# LED_Sectional.net
KiCad netlist of a schematic drawn in EAGLE
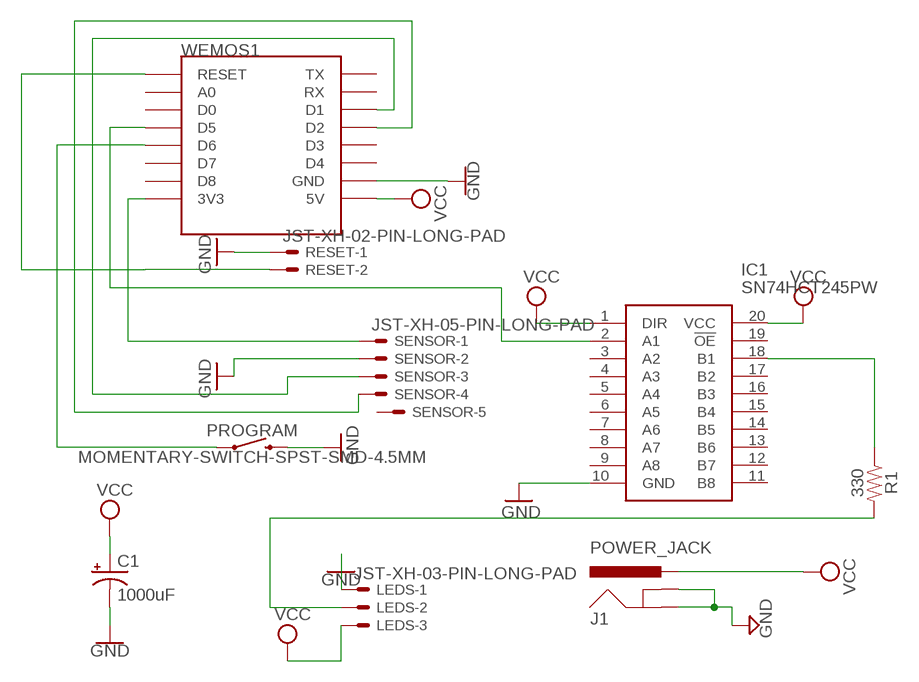
[diagram p0: schematic, sheet 1]

(export (version "E")
  (design (tool "Eeschema 10.0.6"))
  (components
    (comp (ref "C1")
      (value "1000uF")
      (footprint "eagle-import:CT7343")
      (libsource (lib "eagle-import") (part "CPOL-USCT7343"))
    )
    (comp (ref "IC1")
      (value "SN74HCT245PW")
      (footprint "eagle-import:SOP65P640X120-20N")
      (fields
        (field (name "MOUSER_PART_NUMBER") "595-SN74HCT245PW")
        (field (name "RS_PART_NUMBER") "6632287")
      )
      (libsource (lib "eagle-import") (part "SN74HCT245PW"))
    )
    (comp (ref "J1")
      (value "POWER_JACK")
      (footprint "eagle-import:POWER_JACK_PTH")
      (libsource (lib "eagle-import") (part "POWER_JACK"))
    )
    (comp (ref "LEDS")
      (value "JST-XH-03-PIN-LONG-PAD")
      (footprint "eagle-import:JST-XH-03-PACKAGE-LONG-PAD")
      (libsource (lib "eagle-import") (part "JST-XH-03-PIN-LONG-PAD"))
    )
    (comp (ref "PROGRAM")
      (value "MOMENTARY-SWITCH-SPST-SMD-4.5MM")
      (footprint "eagle-import:TACTILE_SWITCH_SMD_4.5MM")
      (libsource (lib "eagle-import") (part "MOMENTARY-SWITCH-SPST-SMD-4.5MM"))
    )
    (comp (ref "R1")
      (value "330")
      (footprint "eagle-import:0603")
      (libsource (lib "eagle-import") (part "330OHM-0603-1/10W-1%"))
    )
    (comp (ref "RESET")
      (value "JST-XH-02-PIN-LONG-PAD")
      (footprint "eagle-import:JST-XH-02-PACKAGE-LONG-PAD")
      (libsource (lib "eagle-import") (part "JST-XH-02-PIN-LONG-PAD"))
    )
    (comp (ref "SENSOR")
      (value "JST-XH-05-PIN-LONG-PAD")
      (footprint "eagle-import:JST-XH-05-PACKAGE-LONG-PAD")
      (libsource (lib "eagle-import") (part "JST-XH-05-PIN-LONG-PAD"))
    )
    (comp (ref "WEMOS1")
      (value "WEMOS-D1-MINI")
      (footprint "eagle-import:WEMOS-D1-MINI")
      (libsource (lib "eagle-import") (part "WEMOS-D1-MINI"))
    )
  )
  (nets
    (net (code "1") (name "GND") (class "Default")
      (node (ref "C1") (pin "-") (pinfunction "-_-") (pintype "passive"))
      (node (ref "IC1") (pin "10") (pinfunction "GND_10") (pintype "bidirectional"))
      (node (ref "J1") (pin "GND") (pinfunction "GND_GND") (pintype "bidirectional"))
      (node (ref "J1") (pin "GNDBREAK") (pinfunction "GNDBREAK_GNDBREAK") (pintype "bidirectional"))
      (node (ref "LEDS") (pin "1") (pinfunction "S_1") (pintype "passive"))
      (node (ref "PROGRAM") (pin "1") (pinfunction "2_1") (pintype "passive"))
      (node (ref "PROGRAM") (pin "4") (pinfunction "2_4") (pintype "passive"))
      (node (ref "RESET") (pin "1") (pinfunction "S_1") (pintype "passive"))
      (node (ref "SENSOR") (pin "2") (pinfunction "S_2") (pintype "passive"))
      (node (ref "WEMOS1") (pin "GND") (pinfunction "GND_GND") (pintype "bidirectional"))
    )
    (net (code "2") (name "Net-(IC1-A1)") (class "Default")
      (node (ref "IC1") (pin "2") (pinfunction "A1_2") (pintype "bidirectional"))
      (node (ref "WEMOS1") (pin "D5") (pinfunction "D5_D5") (pintype "bidirectional"))
    )
    (net (code "3") (name "Net-(IC1-B1)") (class "Default")
      (node (ref "IC1") (pin "18") (pinfunction "B1_18") (pintype "bidirectional"))
      (node (ref "R1") (pin "1") (pinfunction "1_1") (pintype "passive"))
    )
    (net (code "4") (name "Net-(LEDSB-S)") (class "Default")
      (node (ref "LEDS") (pin "2") (pinfunction "S_2") (pintype "passive"))
      (node (ref "R1") (pin "2") (pinfunction "2_2") (pintype "passive"))
    )
    (net (code "5") (name "Net-(PROGRAM-1-Pad2)") (class "Default")
      (node (ref "PROGRAM") (pin "2") (pinfunction "1_2") (pintype "passive"))
      (node (ref "PROGRAM") (pin "3") (pinfunction "1_3") (pintype "passive"))
      (node (ref "WEMOS1") (pin "D6") (pinfunction "D6_D6") (pintype "bidirectional"))
    )
    (net (code "6") (name "Net-(RESETB-S)") (class "Default")
      (node (ref "RESET") (pin "2") (pinfunction "S_2") (pintype "passive"))
      (node (ref "WEMOS1") (pin "RESET") (pinfunction "RESET_RESET") (pintype "bidirectional"))
    )
    (net (code "7") (name "Net-(SENSORA-S)") (class "Default")
      (node (ref "SENSOR") (pin "1") (pinfunction "S_1") (pintype "passive"))
      (node (ref "WEMOS1") (pin "3V3") (pinfunction "3V3_3V3") (pintype "bidirectional"))
    )
    (net (code "8") (name "Net-(SENSORC-S)") (class "Default")
      (node (ref "SENSOR") (pin "3") (pinfunction "S_3") (pintype "passive"))
      (node (ref "WEMOS1") (pin "D1") (pinfunction "D1_D1") (pintype "bidirectional"))
    )
    (net (code "9") (name "Net-(SENSORD-S)") (class "Default")
      (node (ref "SENSOR") (pin "4") (pinfunction "S_4") (pintype "passive"))
      (node (ref "WEMOS1") (pin "D2") (pinfunction "D2_D2") (pintype "bidirectional"))
    )
    (net (code "10") (name "VCC") (class "Default")
      (node (ref "C1") (pin "+") (pinfunction "+_+") (pintype "passive"))
      (node (ref "IC1") (pin "1") (pinfunction "DIR_1") (pintype "bidirectional"))
      (node (ref "IC1") (pin "20") (pinfunction "VCC_20") (pintype "bidirectional"))
      (node (ref "J1") (pin "PWR") (pinfunction "PWR_PWR") (pintype "bidirectional"))
      (node (ref "LEDS") (pin "3") (pinfunction "S_3") (pintype "passive"))
      (node (ref "WEMOS1") (pin "5V") (pinfunction "5V_5V") (pintype "bidirectional"))
    )
    (net (code "11") (name "unconnected-(IC1-A2-Pad3)") (class "Default")
      (node (ref "IC1") (pin "3") (pinfunction "A2_3") (pintype "bidirectional"))
    )
    (net (code "12") (name "unconnected-(IC1-A3-Pad4)") (class "Default")
      (node (ref "IC1") (pin "4") (pinfunction "A3_4") (pintype "bidirectional"))
    )
    (net (code "13") (name "unconnected-(IC1-A4-Pad5)") (class "Default")
      (node (ref "IC1") (pin "5") (pinfunction "A4_5") (pintype "bidirectional"))
    )
    (net (code "14") (name "unconnected-(IC1-A5-Pad6)") (class "Default")
      (node (ref "IC1") (pin "6") (pinfunction "A5_6") (pintype "bidirectional"))
    )
    (net (code "15") (name "unconnected-(IC1-A6-Pad7)") (class "Default")
      (node (ref "IC1") (pin "7") (pinfunction "A6_7") (pintype "bidirectional"))
    )
    (net (code "16") (name "unconnected-(IC1-A7-Pad8)") (class "Default")
      (node (ref "IC1") (pin "8") (pinfunction "A7_8") (pintype "bidirectional"))
    )
    (net (code "17") (name "unconnected-(IC1-A8-Pad9)") (class "Default")
      (node (ref "IC1") (pin "9") (pinfunction "A8_9") (pintype "bidirectional"))
    )
    (net (code "18") (name "unconnected-(IC1-B2-Pad17)") (class "Default")
      (node (ref "IC1") (pin "17") (pinfunction "B2_17") (pintype "bidirectional"))
    )
    (net (code "19") (name "unconnected-(IC1-B3-Pad16)") (class "Default")
      (node (ref "IC1") (pin "16") (pinfunction "B3_16") (pintype "bidirectional"))
    )
    (net (code "20") (name "unconnected-(IC1-B4-Pad15)") (class "Default")
      (node (ref "IC1") (pin "15") (pinfunction "B4_15") (pintype "bidirectional"))
    )
    (net (code "21") (name "unconnected-(IC1-B5-Pad14)") (class "Default")
      (node (ref "IC1") (pin "14") (pinfunction "B5_14") (pintype "bidirectional"))
    )
    (net (code "22") (name "unconnected-(IC1-B6-Pad13)") (class "Default")
      (node (ref "IC1") (pin "13") (pinfunction "B6_13") (pintype "bidirectional"))
    )
    (net (code "23") (name "unconnected-(IC1-B7-Pad12)") (class "Default")
      (node (ref "IC1") (pin "12") (pinfunction "B7_12") (pintype "bidirectional"))
    )
    (net (code "24") (name "unconnected-(IC1-B8-Pad11)") (class "Default")
      (node (ref "IC1") (pin "11") (pinfunction "B8_11") (pintype "bidirectional"))
    )
    (net (code "25") (name "unconnected-(IC1-~{OE}-Pad19)") (class "Default")
      (node (ref "IC1") (pin "19") (pinfunction "~{OE}_19") (pintype "bidirectional"))
    )
    (net (code "26") (name "unconnected-(SENSORE-S-Pad5)") (class "Default")
      (node (ref "SENSOR") (pin "5") (pinfunction "S_5") (pintype "passive"))
    )
    (net (code "27") (name "unconnected-(WEMOS1-PadA0)") (class "Default")
      (node (ref "WEMOS1") (pin "A0") (pinfunction "A0_A0") (pintype "bidirectional"))
    )
    (net (code "28") (name "unconnected-(WEMOS1-PadD0)") (class "Default")
      (node (ref "WEMOS1") (pin "D0") (pinfunction "D0_D0") (pintype "bidirectional"))
    )
    (net (code "29") (name "unconnected-(WEMOS1-PadD3)") (class "Default")
      (node (ref "WEMOS1") (pin "D3") (pinfunction "D3_D3") (pintype "bidirectional"))
    )
    (net (code "30") (name "unconnected-(WEMOS1-PadD4)") (class "Default")
      (node (ref "WEMOS1") (pin "D4") (pinfunction "D4_D4") (pintype "bidirectional"))
    )
    (net (code "31") (name "unconnected-(WEMOS1-PadD7)") (class "Default")
      (node (ref "WEMOS1") (pin "D7") (pinfunction "D7_D7") (pintype "bidirectional"))
    )
    (net (code "32") (name "unconnected-(WEMOS1-PadD8)") (class "Default")
      (node (ref "WEMOS1") (pin "D8") (pinfunction "D8_D8") (pintype "bidirectional"))
    )
    (net (code "33") (name "unconnected-(WEMOS1-PadRX)") (class "Default")
      (node (ref "WEMOS1") (pin "RX") (pinfunction "RX_RX") (pintype "bidirectional"))
    )
    (net (code "34") (name "unconnected-(WEMOS1-PadTX)") (class "Default")
      (node (ref "WEMOS1") (pin "TX") (pinfunction "TX_TX") (pintype "bidirectional"))
    )
  )
)
